# Uebergangsloesung.net
KiCad netlist of a schematic drawn in EAGLE
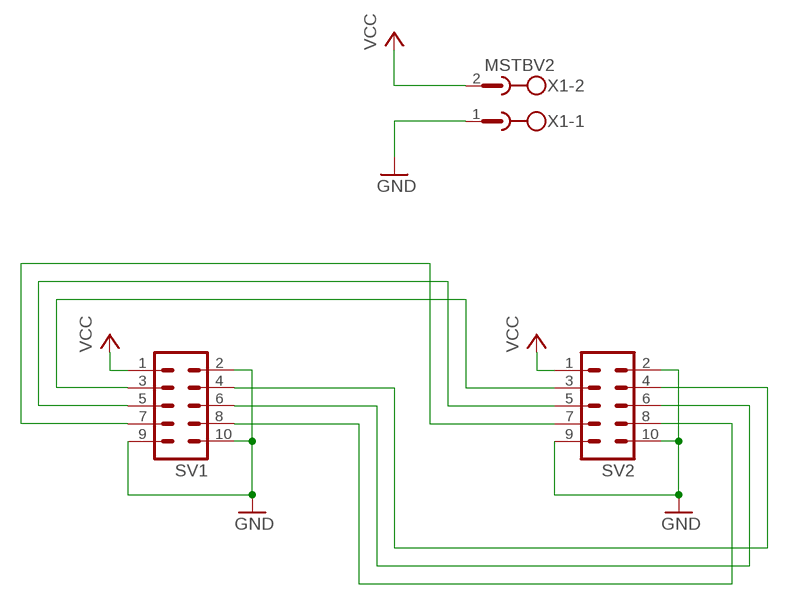
[diagram p0: schematic, sheet 1]

(export (version "E")
  (design (tool "Eeschema 10.0.6"))
  (components
    (comp (ref "SV1")
      (value "ML10")
      (footprint "eagle-import:ML10")
      (libsource (lib "eagle-import") (part "ML10"))
    )
    (comp (ref "SV2")
      (value "ML10")
      (footprint "eagle-import:ML10")
      (libsource (lib "eagle-import") (part "ML10"))
    )
    (comp (ref "X1")
      (value "MSTBV2")
      (footprint "eagle-import:MSTBV2")
      (fields (field (name "MPN") "MSTBV 2,5/2-GF-5.08"))
      (libsource (lib "eagle-import") (part "MSTBV2"))
    )
  )
  (nets
    (net (code "1") (name "GND") (class "Default")
      (node (ref "SV1") (pin "10") (pinfunction "10_10") (pintype "passive"))
      (node (ref "SV1") (pin "2") (pinfunction "2_2") (pintype "passive"))
      (node (ref "SV1") (pin "9") (pinfunction "9_9") (pintype "passive"))
      (node (ref "SV2") (pin "10") (pinfunction "10_10") (pintype "passive"))
      (node (ref "SV2") (pin "2") (pinfunction "2_2") (pintype "passive"))
      (node (ref "SV2") (pin "9") (pinfunction "9_9") (pintype "passive"))
      (node (ref "X1") (pin "1") (pinfunction "1_1") (pintype "passive"))
    )
    (net (code "2") (name "Net-(SV1-Pad3)") (class "Default")
      (node (ref "SV1") (pin "3") (pinfunction "3_3") (pintype "passive"))
      (node (ref "SV2") (pin "3") (pinfunction "3_3") (pintype "passive"))
    )
    (net (code "3") (name "Net-(SV1-Pad4)") (class "Default")
      (node (ref "SV1") (pin "4") (pinfunction "4_4") (pintype "passive"))
      (node (ref "SV2") (pin "4") (pinfunction "4_4") (pintype "passive"))
    )
    (net (code "4") (name "Net-(SV1-Pad5)") (class "Default")
      (node (ref "SV1") (pin "5") (pinfunction "5_5") (pintype "passive"))
      (node (ref "SV2") (pin "5") (pinfunction "5_5") (pintype "passive"))
    )
    (net (code "5") (name "Net-(SV1-Pad6)") (class "Default")
      (node (ref "SV1") (pin "6") (pinfunction "6_6") (pintype "passive"))
      (node (ref "SV2") (pin "6") (pinfunction "6_6") (pintype "passive"))
    )
    (net (code "6") (name "Net-(SV1-Pad7)") (class "Default")
      (node (ref "SV1") (pin "7") (pinfunction "7_7") (pintype "passive"))
      (node (ref "SV2") (pin "7") (pinfunction "7_7") (pintype "passive"))
    )
    (net (code "7") (name "Net-(SV1-Pad8)") (class "Default")
      (node (ref "SV1") (pin "8") (pinfunction "8_8") (pintype "passive"))
      (node (ref "SV2") (pin "8") (pinfunction "8_8") (pintype "passive"))
    )
    (net (code "8") (name "VCC") (class "Default")
      (node (ref "SV1") (pin "1") (pinfunction "1_1") (pintype "passive"))
      (node (ref "SV2") (pin "1") (pinfunction "1_1") (pintype "passive"))
      (node (ref "X1") (pin "2") (pinfunction "1_2") (pintype "passive"))
    )
  )
)
